# fab_academy4.net
KiCad netlist of a schematic drawn in EAGLE
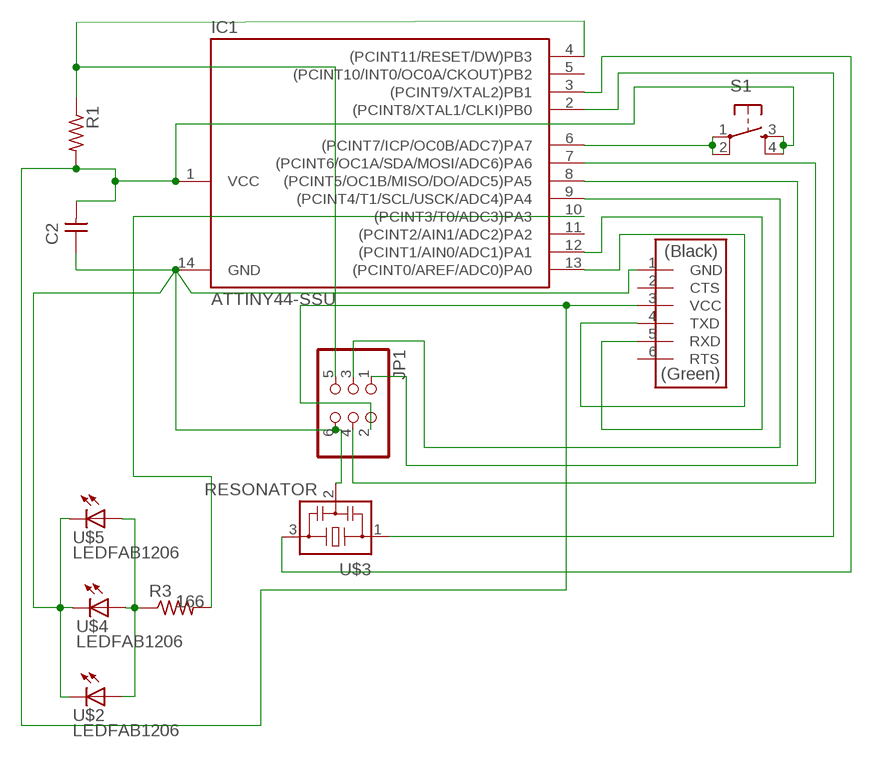
[diagram p0: schematic, sheet 1]

(export (version "E")
  (design (tool "Eeschema 10.0.6"))
  (components
    (comp (ref "C2")
      (value "CAP-UNPOLARIZEDFAB")
      (footprint "eagle-import:C1206FAB")
      (libsource (lib "eagle-import") (part "CAP-UNPOLARIZEDFAB"))
    )
    (comp (ref "IC1")
      (value "ATTINY44-SSU")
      (footprint "eagle-import:SOIC14")
      (libsource (lib "eagle-import") (part "ATTINY44-SSU"))
    )
    (comp (ref "JP1")
      (value "PINHD-2X3-SMD")
      (footprint "eagle-import:2X03SMD")
      (libsource (lib "eagle-import") (part "PINHD-2X3-SMD"))
    )
    (comp (ref "R1")
      (value "RES-US1206FAB")
      (footprint "eagle-import:R1206FAB")
      (libsource (lib "eagle-import") (part "RES-US1206FAB"))
    )
    (comp (ref "R3")
      (value "RES-US1206FAB")
      (footprint "eagle-import:R1206FAB")
      (fields (field (name "RESISTOR") "166"))
      (libsource (lib "eagle-import") (part "RES-US1206FAB"))
    )
    (comp (ref "S1")
      (value "6MM_SWITCH6MM_SWITCH")
      (footprint "eagle-import:6MM_SWITCH")
      (libsource (lib "eagle-import") (part "6MM_SWITCH6MM_SWITCH"))
    )
    (comp (ref "U$1")
      (value "FTDI-SMD-HEADER")
      (footprint "eagle-import:1X06SMD")
      (libsource (lib "eagle-import") (part "FTDI-SMD-HEADER"))
    )
    (comp (ref "U$2")
      (value "LEDFAB1206")
      (footprint "eagle-import:LED1206FAB")
      (libsource (lib "eagle-import") (part "LEDFAB1206"))
    )
    (comp (ref "U$3")
      (value "RESONATOR")
      (footprint "eagle-import:EFOBM")
      (libsource (lib "eagle-import") (part "RESONATOR"))
    )
    (comp (ref "U$4")
      (value "LEDFAB1206")
      (footprint "eagle-import:LED1206FAB")
      (libsource (lib "eagle-import") (part "LEDFAB1206"))
    )
    (comp (ref "U$5")
      (value "LEDFAB1206")
      (footprint "eagle-import:LED1206FAB")
      (libsource (lib "eagle-import") (part "LEDFAB1206"))
    )
  )
  (nets
    (net (code "1") (name "Net-(IC1-(PCINT0{slash}AREF{slash}ADC0)PA0)") (class "Default")
      (node (ref "IC1") (pin "13") (pinfunction "(PCINT0/AREF/ADC0)PA0_13") (pintype "bidirectional"))
      (node (ref "U$1") (pin "4") (pinfunction "TXD_4") (pintype "bidirectional"))
    )
    (net (code "2") (name "Net-(IC1-(PCINT1{slash}AIN0{slash}ADC1)PA1)") (class "Default")
      (node (ref "IC1") (pin "12") (pinfunction "(PCINT1/AIN0/ADC1)PA1_12") (pintype "bidirectional"))
      (node (ref "U$1") (pin "5") (pinfunction "RXD_5") (pintype "bidirectional"))
    )
    (net (code "3") (name "Net-(IC1-(PCINT3{slash}T0{slash}ADC3)PA3)") (class "Default")
      (node (ref "IC1") (pin "10") (pinfunction "(PCINT3/T0/ADC3)PA3_10") (pintype "bidirectional"))
      (node (ref "R3") (pin "2") (pinfunction "2_2") (pintype "passive"))
    )
    (net (code "4") (name "Net-(IC1-(PCINT4{slash}T1{slash}SCL{slash}USCK{slash}ADC4)PA4)") (class "Default")
      (node (ref "IC1") (pin "9") (pinfunction "(PCINT4/T1/SCL/USCK/ADC4)PA4_9") (pintype "bidirectional"))
      (node (ref "JP1") (pin "3") (pinfunction "3_3") (pintype "passive"))
    )
    (net (code "5") (name "Net-(IC1-(PCINT5{slash}OC1B{slash}MISO{slash}DO{slash}ADC5)PA5)") (class "Default")
      (node (ref "IC1") (pin "8") (pinfunction "(PCINT5/OC1B/MISO/DO/ADC5)PA5_8") (pintype "bidirectional"))
      (node (ref "JP1") (pin "1") (pinfunction "1_1") (pintype "passive"))
    )
    (net (code "6") (name "Net-(IC1-(PCINT6{slash}OC1A{slash}SDA{slash}MOSI{slash}ADC6)PA6)") (class "Default")
      (node (ref "IC1") (pin "7") (pinfunction "(PCINT6/OC1A/SDA/MOSI/ADC6)PA6_7") (pintype "bidirectional"))
      (node (ref "JP1") (pin "4") (pinfunction "4_4") (pintype "passive"))
    )
    (net (code "7") (name "Net-(IC1-(PCINT7{slash}ICP{slash}OC0B{slash}ADC7)PA7)") (class "Default")
      (node (ref "IC1") (pin "6") (pinfunction "(PCINT7/ICP/OC0B/ADC7)PA7_6") (pintype "bidirectional"))
      (node (ref "S1") (pin "1") (pinfunction "P_1") (pintype "passive"))
      (node (ref "S1") (pin "2") (pinfunction "P1_2") (pintype "passive"))
    )
    (net (code "8") (name "Net-(IC1-(PCINT8{slash}XTAL1{slash}CLKI)PB0)") (class "Default")
      (node (ref "IC1") (pin "2") (pinfunction "(PCINT8/XTAL1/CLKI)PB0_2") (pintype "bidirectional"))
      (node (ref "U$3") (pin "1") (pinfunction "1_1") (pintype "passive"))
    )
    (net (code "9") (name "Net-(IC1-(PCINT9{slash}XTAL2)PB1)") (class "Default")
      (node (ref "IC1") (pin "3") (pinfunction "(PCINT9/XTAL2)PB1_3") (pintype "bidirectional"))
      (node (ref "U$3") (pin "3") (pinfunction "3_3") (pintype "passive"))
    )
    (net (code "10") (name "Net-(IC1-(PCINT11{slash}RESET{slash}DW)PB3)") (class "Default")
      (node (ref "IC1") (pin "4") (pinfunction "(PCINT11/RESET/DW)PB3_4") (pintype "bidirectional"))
      (node (ref "JP1") (pin "5") (pinfunction "5_5") (pintype "passive"))
      (node (ref "R1") (pin "1") (pinfunction "1_1") (pintype "passive"))
    )
    (net (code "11") (name "Net-(IC1-GND)") (class "Default")
      (node (ref "C2") (pin "1") (pinfunction "1_1") (pintype "passive"))
      (node (ref "IC1") (pin "14") (pinfunction "GND_14") (pintype "power_in"))
      (node (ref "JP1") (pin "6") (pinfunction "6_6") (pintype "passive"))
      (node (ref "U$1") (pin "1") (pinfunction "GND_1") (pintype "bidirectional"))
      (node (ref "U$2") (pin "2") (pinfunction "C_2") (pintype "passive"))
      (node (ref "U$3") (pin "2") (pinfunction "2_2") (pintype "passive"))
      (node (ref "U$4") (pin "2") (pinfunction "C_2") (pintype "passive"))
      (node (ref "U$5") (pin "2") (pinfunction "C_2") (pintype "passive"))
    )
    (net (code "12") (name "Net-(IC1-VCC)") (class "Default")
      (node (ref "C2") (pin "2") (pinfunction "2_2") (pintype "passive"))
      (node (ref "IC1") (pin "1") (pinfunction "VCC_1") (pintype "power_in"))
      (node (ref "JP1") (pin "2") (pinfunction "2_2") (pintype "passive"))
      (node (ref "R1") (pin "2") (pinfunction "2_2") (pintype "passive"))
      (node (ref "S1") (pin "3") (pinfunction "S_3") (pintype "passive"))
      (node (ref "S1") (pin "4") (pinfunction "S1_4") (pintype "passive"))
      (node (ref "U$1") (pin "3") (pinfunction "VCC_3") (pintype "bidirectional"))
    )
    (net (code "13") (name "Net-(U$2-A)") (class "Default")
      (node (ref "R3") (pin "1") (pinfunction "1_1") (pintype "passive"))
      (node (ref "U$2") (pin "1") (pinfunction "A_1") (pintype "passive"))
      (node (ref "U$4") (pin "1") (pinfunction "A_1") (pintype "passive"))
      (node (ref "U$5") (pin "1") (pinfunction "A_1") (pintype "passive"))
    )
    (net (code "14") (name "unconnected-(IC1-(PCINT2{slash}AIN1{slash}ADC2)PA2-Pad11)") (class "Default")
      (node (ref "IC1") (pin "11") (pinfunction "(PCINT2/AIN1/ADC2)PA2_11") (pintype "bidirectional"))
    )
    (net (code "15") (name "unconnected-(IC1-(PCINT10{slash}INT0{slash}OC0A{slash}CKOUT)PB2-Pad5)") (class "Default")
      (node (ref "IC1") (pin "5") (pinfunction "(PCINT10/INT0/OC0A/CKOUT)PB2_5") (pintype "bidirectional"))
    )
    (net (code "16") (name "unconnected-(U$1-CTS-Pad2)") (class "Default")
      (node (ref "U$1") (pin "2") (pinfunction "CTS_2") (pintype "bidirectional"))
    )
    (net (code "17") (name "unconnected-(U$1-RTS-Pad6)") (class "Default")
      (node (ref "U$1") (pin "6") (pinfunction "RTS_6") (pintype "bidirectional"))
    )
  )
)
